# ADC_board_intermittent_design_2.net
KiCad netlist of a schematic drawn in EAGLE
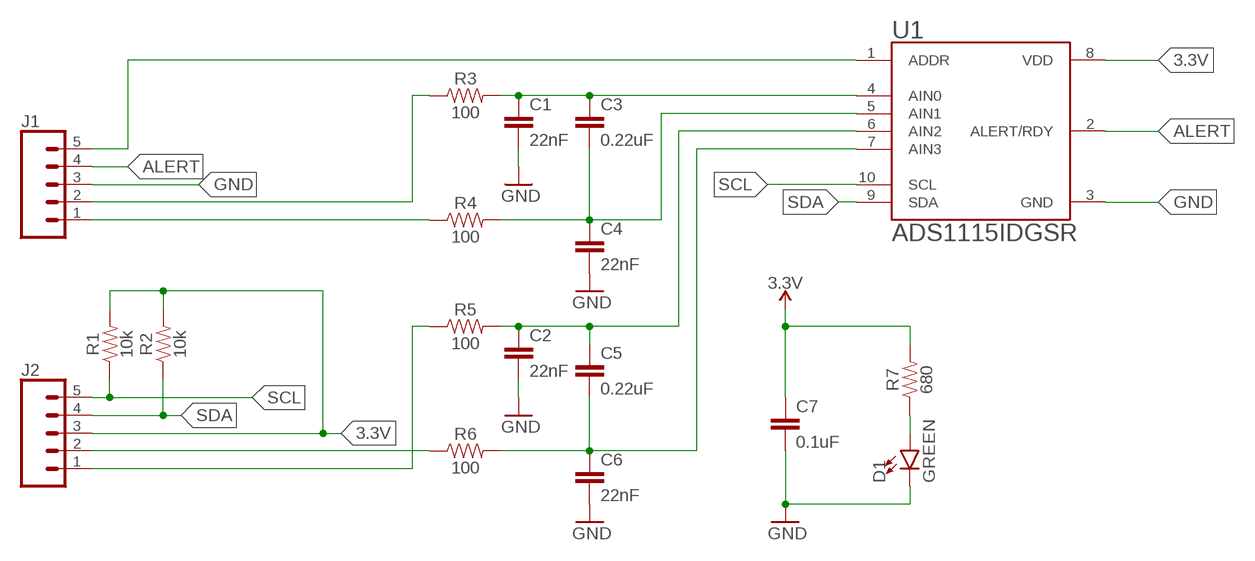
[diagram p0: schematic, sheet 1]

(export (version "E")
  (design (tool "Eeschema 10.0.6"))
  (components
    (comp (ref "C1")
      (value "22nF")
      (footprint "eagle-import:0603")
      (libsource (lib "eagle-import") (part "22NF/22,000PF-0603-50V-10%"))
    )
    (comp (ref "C2")
      (value "22nF")
      (footprint "eagle-import:0603")
      (libsource (lib "eagle-import") (part "22NF/22,000PF-0603-50V-10%"))
    )
    (comp (ref "C3")
      (value "0.22uF")
      (footprint "eagle-import:0603")
      (libsource (lib "eagle-import") (part "0.22UF-0603-25V-10%"))
    )
    (comp (ref "C4")
      (value "22nF")
      (footprint "eagle-import:0603")
      (libsource (lib "eagle-import") (part "22NF/22,000PF-0603-50V-10%"))
    )
    (comp (ref "C5")
      (value "0.22uF")
      (footprint "eagle-import:0603")
      (libsource (lib "eagle-import") (part "0.22UF-0603-25V-10%"))
    )
    (comp (ref "C6")
      (value "22nF")
      (footprint "eagle-import:0603")
      (libsource (lib "eagle-import") (part "22NF/22,000PF-0603-50V-10%"))
    )
    (comp (ref "C7")
      (value "0.1uF")
      (footprint "eagle-import:0402")
      (libsource (lib "eagle-import") (part "0.1UF-0402-16V-10%"))
    )
    (comp (ref "D1")
      (value "GREEN")
      (footprint "eagle-import:LED-0603")
      (libsource (lib "eagle-import") (part "LED-GREEN0603"))
    )
    (comp (ref "J1")
      (value "CONN_05")
      (footprint "eagle-import:1X05")
      (libsource (lib "eagle-import") (part "CONN_05"))
    )
    (comp (ref "J2")
      (value "CONN_05")
      (footprint "eagle-import:1X05")
      (libsource (lib "eagle-import") (part "CONN_05"))
    )
    (comp (ref "R1")
      (value "10k")
      (footprint "eagle-import:0603")
      (libsource (lib "eagle-import") (part "10KOHM-0603-1/10W-1%"))
    )
    (comp (ref "R2")
      (value "10k")
      (footprint "eagle-import:0603")
      (libsource (lib "eagle-import") (part "10KOHM-0603-1/10W-1%"))
    )
    (comp (ref "R3")
      (value "100")
      (footprint "eagle-import:0603")
      (libsource (lib "eagle-import") (part "100OHM-0603-1/4W-5%"))
    )
    (comp (ref "R4")
      (value "100")
      (footprint "eagle-import:0603")
      (libsource (lib "eagle-import") (part "100OHM-0603-1/4W-5%"))
    )
    (comp (ref "R5")
      (value "100")
      (footprint "eagle-import:0603")
      (libsource (lib "eagle-import") (part "100OHM-0603-1/4W-5%"))
    )
    (comp (ref "R6")
      (value "100")
      (footprint "eagle-import:0603")
      (libsource (lib "eagle-import") (part "100OHM-0603-1/4W-5%"))
    )
    (comp (ref "R7")
      (value "680")
      (footprint "eagle-import:0603")
      (libsource (lib "eagle-import") (part "680OHM-0603-1/10W-5%"))
    )
    (comp (ref "U1")
      (value "ADS1115IDGSR")
      (footprint "eagle-import:SOP50P490X110-10N")
      (fields (field (name "DIGI-KEY_PART_NUMBER") "296-38849-1-ND") (field (name "MF") "Texas Instruments"))
      (libsource (lib "eagle-import") (part "ADS1115IDGSR"))
    )
  )
  (nets
    (net (code "1") (name "3.3V") (class "Default")
      (node (ref "C7") (pin "1") (pinfunction "1_1") (pintype "passive"))
      (node (ref "J2") (pin "3") (pinfunction "3_3") (pintype "passive"))
      (node (ref "R1") (pin "2") (pinfunction "2_2") (pintype "passive"))
      (node (ref "R2") (pin "2") (pinfunction "2_2") (pintype "passive"))
      (node (ref "R7") (pin "2") (pinfunction "2_2") (pintype "passive"))
      (node (ref "U1") (pin "8") (pinfunction "VDD_8") (pintype "power_in"))
    )
    (net (code "2") (name "ALERT") (class "Default")
      (node (ref "J1") (pin "4") (pinfunction "4_4") (pintype "passive"))
      (node (ref "U1") (pin "2") (pinfunction "ALERT/RDY_2") (pintype "output"))
    )
    (net (code "3") (name "GND") (class "Default")
      (node (ref "C1") (pin "2") (pinfunction "2_2") (pintype "passive"))
      (node (ref "C2") (pin "2") (pinfunction "2_2") (pintype "passive"))
      (node (ref "C4") (pin "2") (pinfunction "2_2") (pintype "passive"))
      (node (ref "C6") (pin "2") (pinfunction "2_2") (pintype "passive"))
      (node (ref "C7") (pin "2") (pinfunction "2_2") (pintype "passive"))
      (node (ref "D1") (pin "C") (pinfunction "C_C") (pintype "passive"))
      (node (ref "J1") (pin "3") (pinfunction "3_3") (pintype "passive"))
      (node (ref "U1") (pin "3") (pinfunction "GND_3") (pintype "power_in"))
    )
    (net (code "4") (name "Net-(D1-PadA)") (class "Default")
      (node (ref "D1") (pin "A") (pinfunction "A_A") (pintype "passive"))
      (node (ref "R7") (pin "1") (pinfunction "1_1") (pintype "passive"))
    )
    (net (code "5") (name "Net-(J1-Pad1)") (class "Default")
      (node (ref "J1") (pin "1") (pinfunction "1_1") (pintype "passive"))
      (node (ref "R4") (pin "1") (pinfunction "1_1") (pintype "passive"))
    )
    (net (code "6") (name "Net-(J1-Pad2)") (class "Default")
      (node (ref "J1") (pin "2") (pinfunction "2_2") (pintype "passive"))
      (node (ref "R3") (pin "1") (pinfunction "1_1") (pintype "passive"))
    )
    (net (code "7") (name "Net-(J2-Pad1)") (class "Default")
      (node (ref "J2") (pin "1") (pinfunction "1_1") (pintype "passive"))
      (node (ref "R5") (pin "1") (pinfunction "1_1") (pintype "passive"))
    )
    (net (code "8") (name "Net-(J2-Pad2)") (class "Default")
      (node (ref "J2") (pin "2") (pinfunction "2_2") (pintype "passive"))
      (node (ref "R6") (pin "1") (pinfunction "1_1") (pintype "passive"))
    )
    (net (code "9") (name "Net-(U1-ADDR)") (class "Default")
      (node (ref "J1") (pin "5") (pinfunction "5_5") (pintype "passive"))
      (node (ref "U1") (pin "1") (pinfunction "ADDR_1") (pintype "input"))
    )
    (net (code "10") (name "Net-(U1-AIN0)") (class "Default")
      (node (ref "C1") (pin "1") (pinfunction "1_1") (pintype "passive"))
      (node (ref "C3") (pin "1") (pinfunction "1_1") (pintype "passive"))
      (node (ref "R3") (pin "2") (pinfunction "2_2") (pintype "passive"))
      (node (ref "U1") (pin "4") (pinfunction "AIN0_4") (pintype "input"))
    )
    (net (code "11") (name "Net-(U1-AIN1)") (class "Default")
      (node (ref "C3") (pin "2") (pinfunction "2_2") (pintype "passive"))
      (node (ref "C4") (pin "1") (pinfunction "1_1") (pintype "passive"))
      (node (ref "R4") (pin "2") (pinfunction "2_2") (pintype "passive"))
      (node (ref "U1") (pin "5") (pinfunction "AIN1_5") (pintype "input"))
    )
    (net (code "12") (name "Net-(U1-AIN2)") (class "Default")
      (node (ref "C2") (pin "1") (pinfunction "1_1") (pintype "passive"))
      (node (ref "C5") (pin "1") (pinfunction "1_1") (pintype "passive"))
      (node (ref "R5") (pin "2") (pinfunction "2_2") (pintype "passive"))
      (node (ref "U1") (pin "6") (pinfunction "AIN2_6") (pintype "input"))
    )
    (net (code "13") (name "Net-(U1-AIN3)") (class "Default")
      (node (ref "C5") (pin "2") (pinfunction "2_2") (pintype "passive"))
      (node (ref "C6") (pin "1") (pinfunction "1_1") (pintype "passive"))
      (node (ref "R6") (pin "2") (pinfunction "2_2") (pintype "passive"))
      (node (ref "U1") (pin "7") (pinfunction "AIN3_7") (pintype "input"))
    )
    (net (code "14") (name "SCL") (class "Default")
      (node (ref "J2") (pin "5") (pinfunction "5_5") (pintype "passive"))
      (node (ref "R1") (pin "1") (pinfunction "1_1") (pintype "passive"))
      (node (ref "U1") (pin "10") (pinfunction "SCL_10") (pintype "input"))
    )
    (net (code "15") (name "SDA") (class "Default")
      (node (ref "J2") (pin "4") (pinfunction "4_4") (pintype "passive"))
      (node (ref "R2") (pin "1") (pinfunction "1_1") (pintype "passive"))
      (node (ref "U1") (pin "9") (pinfunction "SDA_9") (pintype "bidirectional"))
    )
  )
)
